# ibm.net
KiCad netlist of a schematic drawn in EAGLE
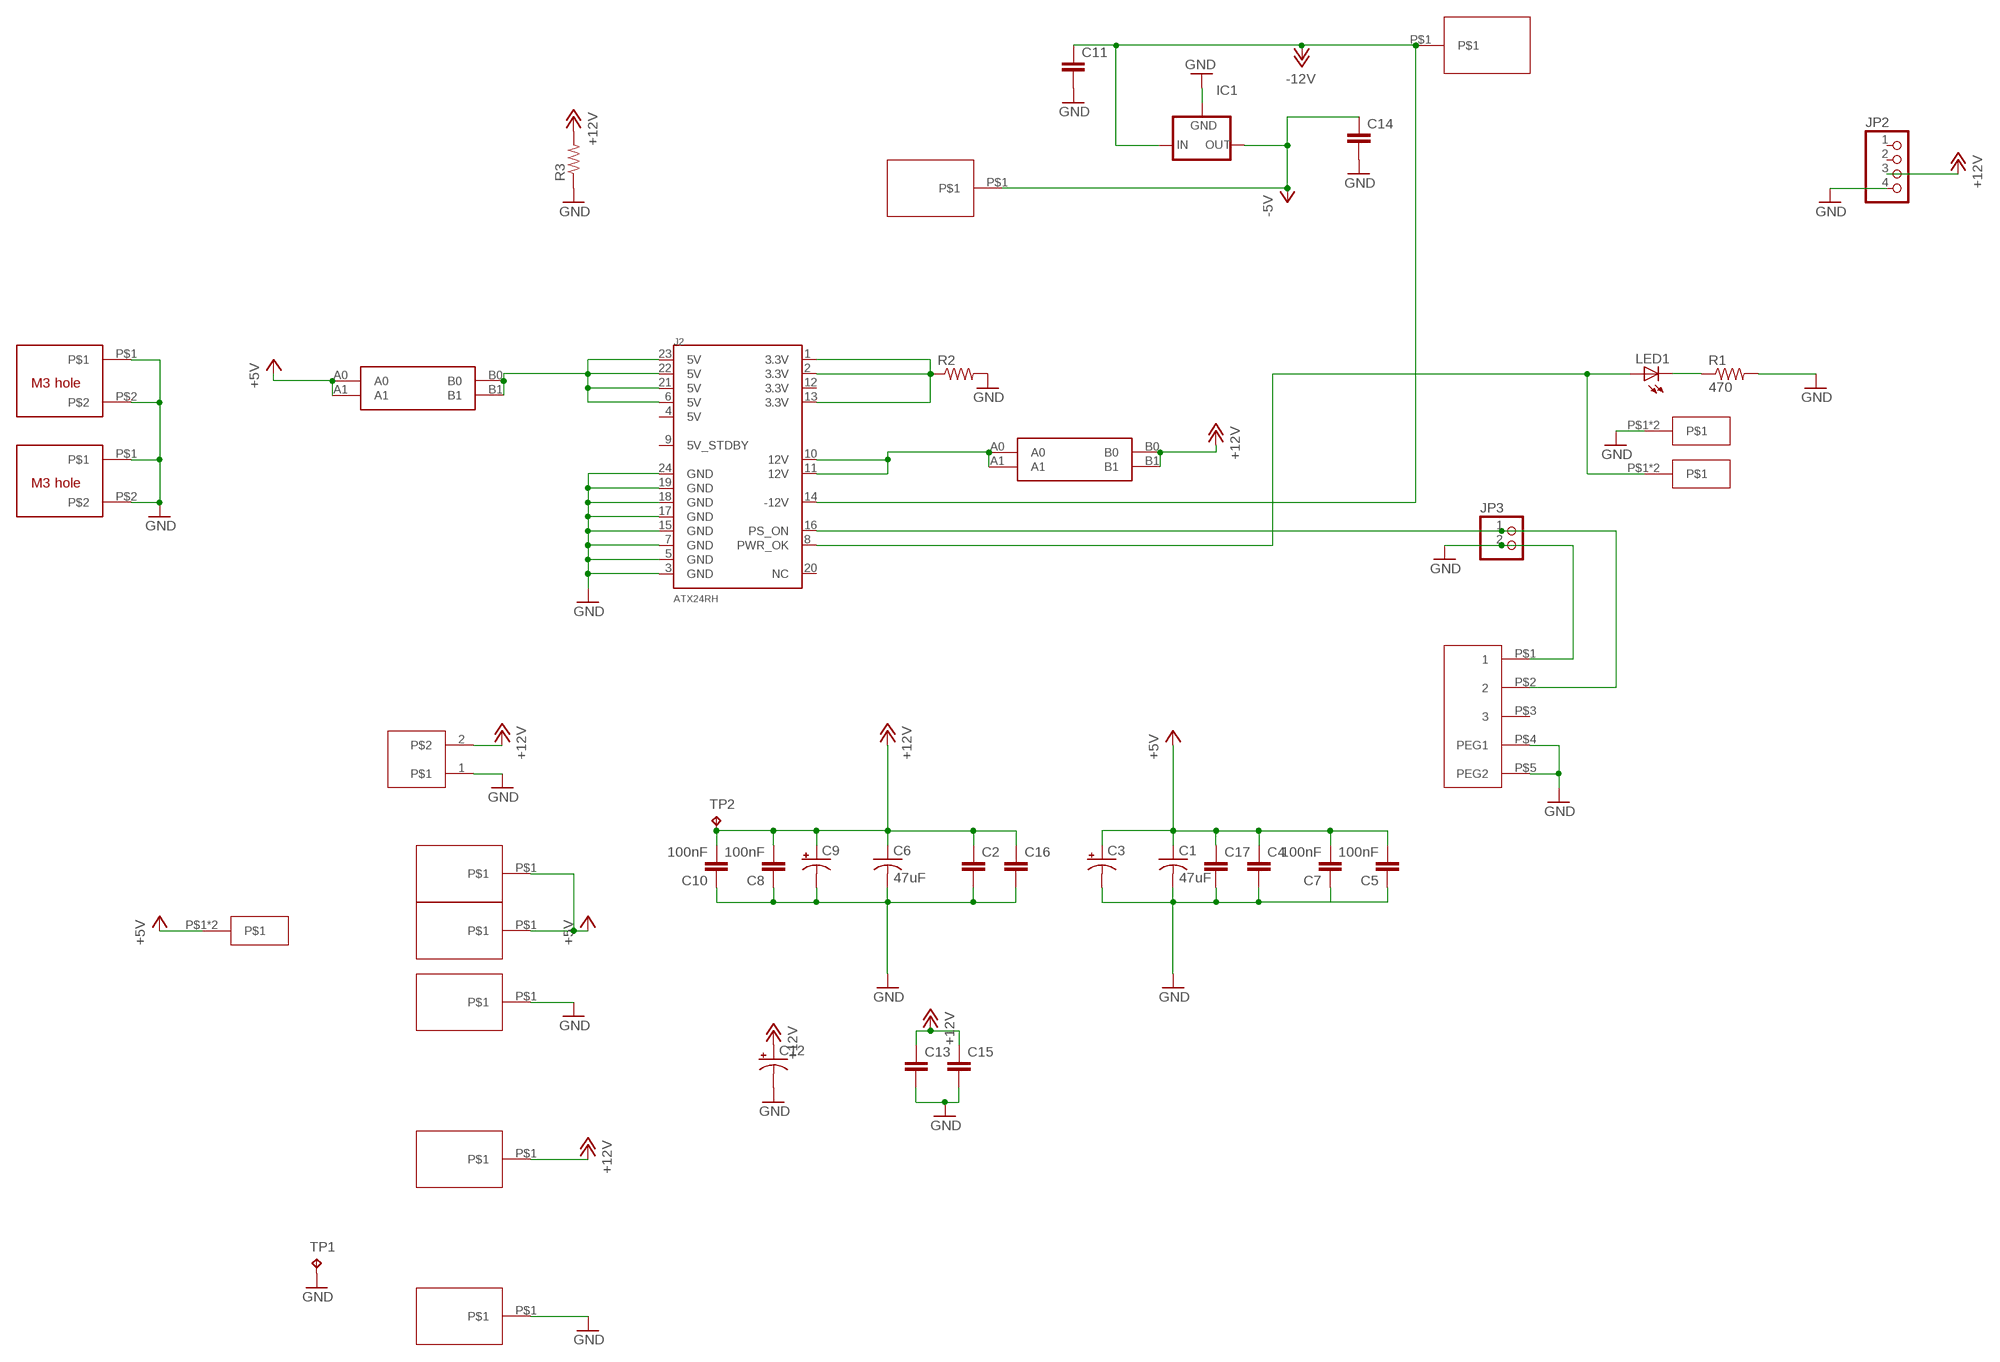
[diagram p0: schematic, sheet 1]

(export (version "E")
  (design (tool "Eeschema 10.0.6"))
  (components
    (comp (ref "C1")
      (value "47uF")
      (footprint "eagle-import:C1210")
      (libsource (lib "eagle-import") (part "C-USC1210"))
    )
    (comp (ref "C2")
      (value "C5/2.5")
      (footprint "eagle-import:C5B2.5")
      (libsource (lib "eagle-import") (part "C5/2.5"))
    )
    (comp (ref "C3")
      (value "CPOL-USE3.5-8")
      (footprint "eagle-import:E3,5-8")
      (libsource (lib "eagle-import") (part "CPOL-USE3.5-8"))
    )
    (comp (ref "C4")
      (value "C5/2.5")
      (footprint "eagle-import:C5B2.5")
      (libsource (lib "eagle-import") (part "C5/2.5"))
    )
    (comp (ref "C5")
      (value "100nF")
      (footprint "eagle-import:0805@1")
      (libsource (lib "eagle-import") (part "CAP0805"))
    )
    (comp (ref "C6")
      (value "47uF")
      (footprint "eagle-import:C1210")
      (libsource (lib "eagle-import") (part "C-USC1210"))
    )
    (comp (ref "C7")
      (value "100nF")
      (footprint "eagle-import:0805@1")
      (libsource (lib "eagle-import") (part "CAP0805"))
    )
    (comp (ref "C8")
      (value "100nF")
      (footprint "eagle-import:0805@1")
      (libsource (lib "eagle-import") (part "CAP0805"))
    )
    (comp (ref "C9")
      (value "CPOL-USE3.5-8")
      (footprint "eagle-import:E3,5-8")
      (libsource (lib "eagle-import") (part "CPOL-USE3.5-8"))
    )
    (comp (ref "C10")
      (value "100nF")
      (footprint "eagle-import:0805@1")
      (libsource (lib "eagle-import") (part "CAP0805"))
    )
    (comp (ref "C11")
      (value "C5/2.5")
      (footprint "eagle-import:C5B2.5")
      (libsource (lib "eagle-import") (part "C5/2.5"))
    )
    (comp (ref "C12")
      (value "CPOL-USE3.5-8")
      (footprint "eagle-import:E3,5-8")
      (libsource (lib "eagle-import") (part "CPOL-USE3.5-8"))
    )
    (comp (ref "C13")
      (value "C5/2.5")
      (footprint "eagle-import:C5B2.5")
      (libsource (lib "eagle-import") (part "C5/2.5"))
    )
    (comp (ref "C14")
      (value "C5/2.5")
      (footprint "eagle-import:C5B2.5")
      (libsource (lib "eagle-import") (part "C5/2.5"))
    )
    (comp (ref "C15")
      (value "C5/2.5")
      (footprint "eagle-import:C5B2.5")
      (libsource (lib "eagle-import") (part "C5/2.5"))
    )
    (comp (ref "C16")
      (value "C5/2.5")
      (footprint "eagle-import:C5B2.5")
      (libsource (lib "eagle-import") (part "C5/2.5"))
    )
    (comp (ref "C17")
      (value "C5/2.5")
      (footprint "eagle-import:C5B2.5")
      (libsource (lib "eagle-import") (part "C5/2.5"))
    )
    (comp (ref "IC1")
      (value "79XXS")
      (footprint "eagle-import:79XXS")
      (libsource (lib "eagle-import") (part "79XXS"))
    )
    (comp (ref "J2")
      (value "ATX24RH")
      (footprint "eagle-import:ATX24_RIGHT_ANGLE")
      (libsource (lib "eagle-import") (part "ATX24RH"))
    )
    (comp (ref "JP2")
      (value "PINHD-1X4/90")
      (footprint "eagle-import:1X04_90")
      (libsource (lib "eagle-import") (part "PINHD-1X4/90"))
    )
    (comp (ref "JP3")
      (value "PINHD-1X2/90")
      (footprint "eagle-import:1X02_90")
      (libsource (lib "eagle-import") (part "PINHD-1X2/90"))
    )
    (comp (ref "LED1")
      (value "LED5MM")
      (footprint "eagle-import:LED5MM")
      (libsource (lib "eagle-import") (part "LED5MM"))
    )
    (comp (ref "R1")
      (value "470")
      (footprint "eagle-import:0207_10")
      (libsource (lib "eagle-import") (part "R-US_0207/10"))
    )
    (comp (ref "R2")
      (value "R-US_0411/15")
      (footprint "eagle-import:0411_15")
      (libsource (lib "eagle-import") (part "adafruit_changed_R-US_0411/15"))
    )
    (comp (ref "R3")
      (value "R-US_0411/15")
      (footprint "eagle-import:0411_15")
      (libsource (lib "eagle-import") (part "adafruit_changed_R-US_0411/15"))
    )
    (comp (ref "TP1")
      (value "TPPAD1-13")
      (footprint "eagle-import:P1-13")
      (libsource (lib "eagle-import") (part "TPPAD1-13"))
    )
    (comp (ref "TP2")
      (value "TPPAD1-13")
      (footprint "eagle-import:P1-13")
      (libsource (lib "eagle-import") (part "TPPAD1-13"))
    )
    (comp (ref "U$1")
      (value "ISA")
      (footprint "eagle-import:ISAPAD")
      (libsource (lib "eagle-import") (part "ISA"))
    )
    (comp (ref "U$2")
      (value "CAR_FUSE_HOLDER3IN1")
      (footprint "eagle-import:FUSE_HOLDER_3IN1")
      (libsource (lib "eagle-import") (part "CAR_FUSE_HOLDER3IN1"))
    )
    (comp (ref "U$3")
      (value "28FLAG")
      (footprint "eagle-import:2.8FLAG")
      (libsource (lib "eagle-import") (part "28FLAG"))
    )
    (comp (ref "U$4")
      (value "ROCKSW")
      (footprint "eagle-import:ROCKSW")
      (libsource (lib "eagle-import") (part "ROCKSW"))
    )
    (comp (ref "U$5")
      (value "M3_MOUNTING_HOLE")
      (footprint "eagle-import:M3_MOUNTING_HOLE_PACK")
      (libsource (lib "eagle-import") (part "M3_MOUNTING_HOLE"))
    )
    (comp (ref "U$6")
      (value "M3_MOUNTING_HOLE")
      (footprint "eagle-import:M3_MOUNTING_HOLE_PACK")
      (libsource (lib "eagle-import") (part "M3_MOUNTING_HOLE"))
    )
    (comp (ref "U$7")
      (value "ISA")
      (footprint "eagle-import:ISAPAD")
      (libsource (lib "eagle-import") (part "ISA"))
    )
    (comp (ref "U$8")
      (value "CAR_FUSE_HOLDER3IN1")
      (footprint "eagle-import:FUSE_HOLDER_3IN1")
      (libsource (lib "eagle-import") (part "CAR_FUSE_HOLDER3IN1"))
    )
    (comp (ref "U$9")
      (value "ISA")
      (footprint "eagle-import:ISAPAD")
      (libsource (lib "eagle-import") (part "ISA"))
    )
    (comp (ref "U$10")
      (value "ISA")
      (footprint "eagle-import:ISAPAD")
      (libsource (lib "eagle-import") (part "ISA"))
    )
    (comp (ref "U$11")
      (value "28FLAG")
      (footprint "eagle-import:2.8FLAG")
      (libsource (lib "eagle-import") (part "28FLAG"))
    )
    (comp (ref "U$12")
      (value "CRT2P")
      (footprint "eagle-import:CRT2P")
      (libsource (lib "eagle-import") (part "CRT2P"))
    )
    (comp (ref "U$13")
      (value "ISA")
      (footprint "eagle-import:ISAPAD")
      (libsource (lib "eagle-import") (part "ISA"))
    )
    (comp (ref "U$14")
      (value "28FLAG")
      (footprint "eagle-import:2.8FLAG")
      (libsource (lib "eagle-import") (part "28FLAG"))
    )
    (comp (ref "U$15")
      (value "ISA")
      (footprint "eagle-import:ISAPAD")
      (libsource (lib "eagle-import") (part "ISA"))
    )
    (comp (ref "U$16")
      (value "ISA")
      (footprint "eagle-import:ISAPAD")
      (libsource (lib "eagle-import") (part "ISA"))
    )
  )
  (nets
    (net (code "1") (name "+5V") (class "Default")
      (node (ref "C1") (pin "1") (pinfunction "1_1") (pintype "passive"))
      (node (ref "C17") (pin "1") (pinfunction "1_1") (pintype "passive"))
      (node (ref "C3") (pin "+") (pinfunction "+_+") (pintype "passive"))
      (node (ref "C4") (pin "1") (pinfunction "1_1") (pintype "passive"))
      (node (ref "C5") (pin "2") (pinfunction "2_2") (pintype "passive"))
      (node (ref "C7") (pin "2") (pinfunction "2_2") (pintype "passive"))
      (node (ref "U$1") (pin "P$1") (pinfunction "P$1_P$1") (pintype "bidirectional"))
      (node (ref "U$11") (pin "P$1") (pinfunction "P$1_P$1") (pintype "bidirectional"))
      (node (ref "U$11") (pin "P$2") (pinfunction "P$1_P$2") (pintype "bidirectional"))
      (node (ref "U$16") (pin "P$1") (pinfunction "P$1_P$1") (pintype "bidirectional"))
      (node (ref "U$8") (pin "A0") (pinfunction "A0_A0") (pintype "bidirectional"))
      (node (ref "U$8") (pin "A1") (pinfunction "A1_A1") (pintype "bidirectional"))
    )
    (net (code "2") (name "+12V") (class "Default")
      (node (ref "C10") (pin "2") (pinfunction "2_2") (pintype "passive"))
      (node (ref "C12") (pin "+") (pinfunction "+_+") (pintype "passive"))
      (node (ref "C13") (pin "1") (pinfunction "1_1") (pintype "passive"))
      (node (ref "C15") (pin "1") (pinfunction "1_1") (pintype "passive"))
      (node (ref "C16") (pin "1") (pinfunction "1_1") (pintype "passive"))
      (node (ref "C2") (pin "1") (pinfunction "1_1") (pintype "passive"))
      (node (ref "C6") (pin "1") (pinfunction "1_1") (pintype "passive"))
      (node (ref "C8") (pin "2") (pinfunction "2_2") (pintype "passive"))
      (node (ref "C9") (pin "+") (pinfunction "+_+") (pintype "passive"))
      (node (ref "JP2") (pin "3") (pinfunction "3_3") (pintype "passive"))
      (node (ref "R3") (pin "2") (pinfunction "2_2") (pintype "passive"))
      (node (ref "TP2") (pin "TP") (pinfunction "TP_TP") (pintype "input"))
      (node (ref "U$12") (pin "2") (pinfunction "P$2_2") (pintype "bidirectional"))
      (node (ref "U$13") (pin "P$1") (pinfunction "P$1_P$1") (pintype "bidirectional"))
      (node (ref "U$2") (pin "B0") (pinfunction "B0_B0") (pintype "bidirectional"))
      (node (ref "U$2") (pin "B1") (pinfunction "B1_B1") (pintype "bidirectional"))
    )
    (net (code "3") (name "-5V") (class "Default")
      (node (ref "C14") (pin "1") (pinfunction "1_1") (pintype "passive"))
      (node (ref "IC1") (pin "OUT") (pinfunction "OUT_OUT") (pintype "passive"))
      (node (ref "U$7") (pin "P$1") (pinfunction "P$1_P$1") (pintype "bidirectional"))
    )
    (net (code "4") (name "-12V") (class "Default")
      (node (ref "C11") (pin "1") (pinfunction "1_1") (pintype "passive"))
      (node (ref "IC1") (pin "IN") (pinfunction "IN_IN") (pintype "input"))
      (node (ref "J2") (pin "14") (pinfunction "-12V_14") (pintype "bidirectional"))
      (node (ref "U$10") (pin "P$1") (pinfunction "P$1_P$1") (pintype "bidirectional"))
    )
    (net (code "5") (name "GND") (class "Default")
      (node (ref "C1") (pin "2") (pinfunction "2_2") (pintype "passive"))
      (node (ref "C10") (pin "1") (pinfunction "1_1") (pintype "passive"))
      (node (ref "C11") (pin "2") (pinfunction "2_2") (pintype "passive"))
      (node (ref "C12") (pin "-") (pinfunction "-_-") (pintype "passive"))
      (node (ref "C13") (pin "2") (pinfunction "2_2") (pintype "passive"))
      (node (ref "C14") (pin "2") (pinfunction "2_2") (pintype "passive"))
      (node (ref "C15") (pin "2") (pinfunction "2_2") (pintype "passive"))
      (node (ref "C16") (pin "2") (pinfunction "2_2") (pintype "passive"))
      (node (ref "C17") (pin "2") (pinfunction "2_2") (pintype "passive"))
      (node (ref "C2") (pin "2") (pinfunction "2_2") (pintype "passive"))
      (node (ref "C3") (pin "-") (pinfunction "-_-") (pintype "passive"))
      (node (ref "C4") (pin "2") (pinfunction "2_2") (pintype "passive"))
      (node (ref "C5") (pin "1") (pinfunction "1_1") (pintype "passive"))
      (node (ref "C6") (pin "2") (pinfunction "2_2") (pintype "passive"))
      (node (ref "C7") (pin "1") (pinfunction "1_1") (pintype "passive"))
      (node (ref "C8") (pin "1") (pinfunction "1_1") (pintype "passive"))
      (node (ref "C9") (pin "-") (pinfunction "-_-") (pintype "passive"))
      (node (ref "IC1") (pin "GND") (pinfunction "GND_GND") (pintype "input"))
      (node (ref "J2") (pin "15") (pinfunction "GND_15") (pintype "bidirectional"))
      (node (ref "J2") (pin "17") (pinfunction "GND_17") (pintype "bidirectional"))
      (node (ref "J2") (pin "18") (pinfunction "GND_18") (pintype "bidirectional"))
      (node (ref "J2") (pin "19") (pinfunction "GND_19") (pintype "bidirectional"))
      (node (ref "J2") (pin "24") (pinfunction "GND_24") (pintype "bidirectional"))
      (node (ref "J2") (pin "3") (pinfunction "GND_3") (pintype "bidirectional"))
      (node (ref "J2") (pin "5") (pinfunction "GND_5") (pintype "bidirectional"))
      (node (ref "J2") (pin "7") (pinfunction "GND_7") (pintype "bidirectional"))
      (node (ref "JP2") (pin "4") (pinfunction "4_4") (pintype "passive"))
      (node (ref "JP3") (pin "2") (pinfunction "2_2") (pintype "passive"))
      (node (ref "R1") (pin "2") (pinfunction "2_2") (pintype "passive"))
      (node (ref "R2") (pin "2") (pinfunction "2_2") (pintype "passive"))
      (node (ref "R3") (pin "1") (pinfunction "1_1") (pintype "passive"))
      (node (ref "TP1") (pin "TP") (pinfunction "TP_TP") (pintype "input"))
      (node (ref "U$12") (pin "1") (pinfunction "P$1_1") (pintype "bidirectional"))
      (node (ref "U$14") (pin "P$1") (pinfunction "P$1_P$1") (pintype "bidirectional"))
      (node (ref "U$14") (pin "P$2") (pinfunction "P$1_P$2") (pintype "bidirectional"))
      (node (ref "U$15") (pin "P$1") (pinfunction "P$1_P$1") (pintype "bidirectional"))
      (node (ref "U$4") (pin "P$1") (pinfunction "1_P$1") (pintype "bidirectional"))
      (node (ref "U$4") (pin "P$4") (pinfunction "PEG1_P$4") (pintype "bidirectional"))
      (node (ref "U$4") (pin "P$5") (pinfunction "PEG2_P$5") (pintype "bidirectional"))
      (node (ref "U$5") (pin "P$1") (pinfunction "P$1_P$1") (pintype "bidirectional"))
      (node (ref "U$5") (pin "P$2") (pinfunction "P$2_P$2") (pintype "bidirectional"))
      (node (ref "U$6") (pin "P$1") (pinfunction "P$1_P$1") (pintype "bidirectional"))
      (node (ref "U$6") (pin "P$2") (pinfunction "P$2_P$2") (pintype "bidirectional"))
      (node (ref "U$9") (pin "P$1") (pinfunction "P$1_P$1") (pintype "bidirectional"))
    )
    (net (code "6") (name "Net-(J2-3.3V-Pad1)") (class "Default")
      (node (ref "J2") (pin "1") (pinfunction "3.3V_1") (pintype "bidirectional"))
      (node (ref "J2") (pin "13") (pinfunction "3.3V_13") (pintype "bidirectional"))
      (node (ref "J2") (pin "2") (pinfunction "3.3V_2") (pintype "bidirectional"))
      (node (ref "R2") (pin "1") (pinfunction "1_1") (pintype "passive"))
    )
    (net (code "7") (name "Net-(J2-5V-Pad21)") (class "Default")
      (node (ref "J2") (pin "21") (pinfunction "5V_21") (pintype "bidirectional"))
      (node (ref "J2") (pin "22") (pinfunction "5V_22") (pintype "bidirectional"))
      (node (ref "J2") (pin "23") (pinfunction "5V_23") (pintype "bidirectional"))
      (node (ref "J2") (pin "6") (pinfunction "5V_6") (pintype "bidirectional"))
      (node (ref "U$8") (pin "B0") (pinfunction "B0_B0") (pintype "bidirectional"))
      (node (ref "U$8") (pin "B1") (pinfunction "B1_B1") (pintype "bidirectional"))
    )
    (net (code "8") (name "Net-(J2-12V-Pad10)") (class "Default")
      (node (ref "J2") (pin "10") (pinfunction "12V_10") (pintype "bidirectional"))
      (node (ref "J2") (pin "11") (pinfunction "12V_11") (pintype "bidirectional"))
      (node (ref "U$2") (pin "A0") (pinfunction "A0_A0") (pintype "bidirectional"))
      (node (ref "U$2") (pin "A1") (pinfunction "A1_A1") (pintype "bidirectional"))
    )
    (net (code "9") (name "Net-(J2-PS_ON)") (class "Default")
      (node (ref "J2") (pin "16") (pinfunction "PS_ON_16") (pintype "bidirectional"))
      (node (ref "JP3") (pin "1") (pinfunction "1_1") (pintype "passive"))
      (node (ref "U$4") (pin "P$2") (pinfunction "2_P$2") (pintype "bidirectional"))
    )
    (net (code "10") (name "Net-(J2-PWR_OK)") (class "Default")
      (node (ref "J2") (pin "8") (pinfunction "PWR_OK_8") (pintype "bidirectional"))
      (node (ref "LED1") (pin "A") (pinfunction "A_A") (pintype "passive"))
      (node (ref "U$3") (pin "P$1") (pinfunction "P$1_P$1") (pintype "bidirectional"))
      (node (ref "U$3") (pin "P$2") (pinfunction "P$1_P$2") (pintype "bidirectional"))
    )
    (net (code "11") (name "Net-(LED1-C)") (class "Default")
      (node (ref "LED1") (pin "K") (pinfunction "C_K") (pintype "passive"))
      (node (ref "R1") (pin "1") (pinfunction "1_1") (pintype "passive"))
    )
    (net (code "12") (name "unconnected-(J2-3.3V-Pad12)") (class "Default")
      (node (ref "J2") (pin "12") (pinfunction "3.3V_12") (pintype "bidirectional"))
    )
    (net (code "13") (name "unconnected-(J2-5V-Pad4)") (class "Default")
      (node (ref "J2") (pin "4") (pinfunction "5V_4") (pintype "bidirectional"))
    )
    (net (code "14") (name "unconnected-(J2-5V_STDBY-Pad9)") (class "Default")
      (node (ref "J2") (pin "9") (pinfunction "5V_STDBY_9") (pintype "bidirectional"))
    )
    (net (code "15") (name "unconnected-(J2-NC-Pad20)") (class "Default")
      (node (ref "J2") (pin "20") (pinfunction "NC_20") (pintype "bidirectional"))
    )
    (net (code "16") (name "unconnected-(JP2-Pad1)") (class "Default")
      (node (ref "JP2") (pin "1") (pinfunction "1_1") (pintype "passive"))
    )
    (net (code "17") (name "unconnected-(JP2-Pad2)") (class "Default")
      (node (ref "JP2") (pin "2") (pinfunction "2_2") (pintype "passive"))
    )
    (net (code "18") (name "unconnected-(U$4-3-PadP$3)") (class "Default")
      (node (ref "U$4") (pin "P$3") (pinfunction "3_P$3") (pintype "bidirectional"))
    )
  )
)
